# BUTTON_LED.net
KiCad netlist of a schematic drawn in Altium Designer
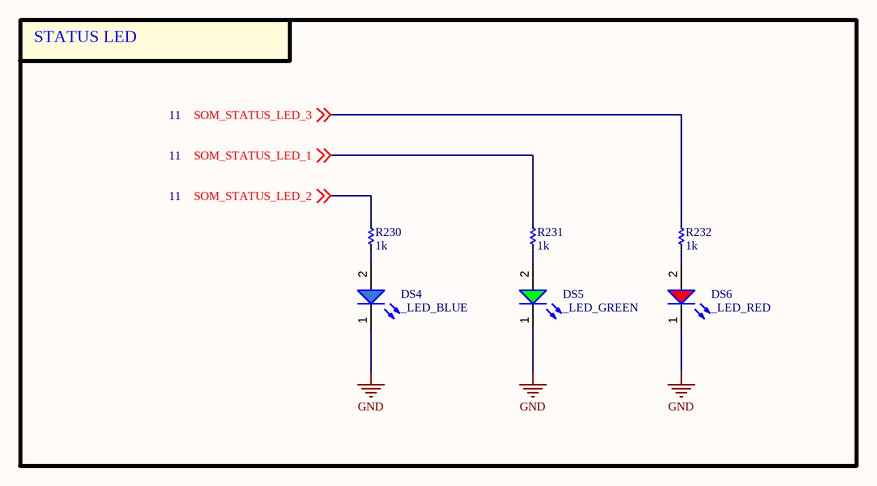
[diagram p0: BUTTON_LED.SchDoc]

(export (version "E")
  (design (tool "Eeschema 10.0.6"))
  (components
    (comp (ref "DS4")
      (value "_LED_BLUE")
      (footprint "LED_0603")
      (description "LED BLUE CLEAR 0603 SMD")
      (libsource (lib "IFBschelib") (part "LED_BLUE"))
    )
    (comp (ref "DS5")
      (value "_LED_GREEN")
      (footprint "LED_0603")
      (description "LED GREEN CLEAR 0603 SMD")
      (libsource (lib "IFBschelib") (part "LED_GREEN"))
    )
    (comp (ref "DS6")
      (value "_LED_RED")
      (footprint "LED_0603")
      (description "LED RED CLEAR 0603 SMD")
      (libsource (lib "IFBschelib") (part "LED_RED"))
    )
    (comp (ref "R230")
      (value "1k")
      (footprint "RES_C_1005x30_L")
      (description "RES")
      (libsource (lib "LABLIB") (part "_RES_B_2"))
    )
    (comp (ref "R231")
      (value "1k")
      (footprint "RES_C_1005x30_L")
      (description "RES")
      (libsource (lib "LABLIB") (part "_RES_B_2"))
    )
    (comp (ref "R232")
      (value "1k")
      (footprint "RES_C_1005x30_L")
      (description "RES")
      (libsource (lib "LABLIB") (part "_RES_B_2"))
    )
  )
  (nets
    (net (code "1") (name "GND") (class "Default")
      (node (ref "DS4") (pin "1") (pinfunction "K_1") (pintype "passive"))
      (node (ref "DS5") (pin "1") (pinfunction "K_1") (pintype "passive"))
      (node (ref "DS6") (pin "1") (pinfunction "K_1") (pintype "passive"))
    )
    (net (code "2") (name "Net-(DS4-A)") (class "Default")
      (node (ref "DS4") (pin "2") (pinfunction "A_2") (pintype "passive"))
      (node (ref "R230") (pin "1") (pinfunction "1_1") (pintype "passive"))
    )
    (net (code "3") (name "Net-(DS5-A)") (class "Default")
      (node (ref "DS5") (pin "2") (pinfunction "A_2") (pintype "passive"))
      (node (ref "R231") (pin "1") (pinfunction "1_1") (pintype "passive"))
    )
    (net (code "4") (name "Net-(DS6-A)") (class "Default")
      (node (ref "DS6") (pin "2") (pinfunction "A_2") (pintype "passive"))
      (node (ref "R232") (pin "1") (pinfunction "1_1") (pintype "passive"))
    )
    (net (code "5") (name "SOM_STATUS_LED_1") (class "Default")
      (node (ref "R231") (pin "2") (pinfunction "2_2") (pintype "passive"))
    )
    (net (code "6") (name "SOM_STATUS_LED_2") (class "Default")
      (node (ref "R230") (pin "2") (pinfunction "2_2") (pintype "passive"))
    )
    (net (code "7") (name "SOM_STATUS_LED_3") (class "Default")
      (node (ref "R232") (pin "2") (pinfunction "2_2") (pintype "passive"))
    )
  )
)
